# MCU.net
KiCad netlist of a schematic drawn in Altium Designer
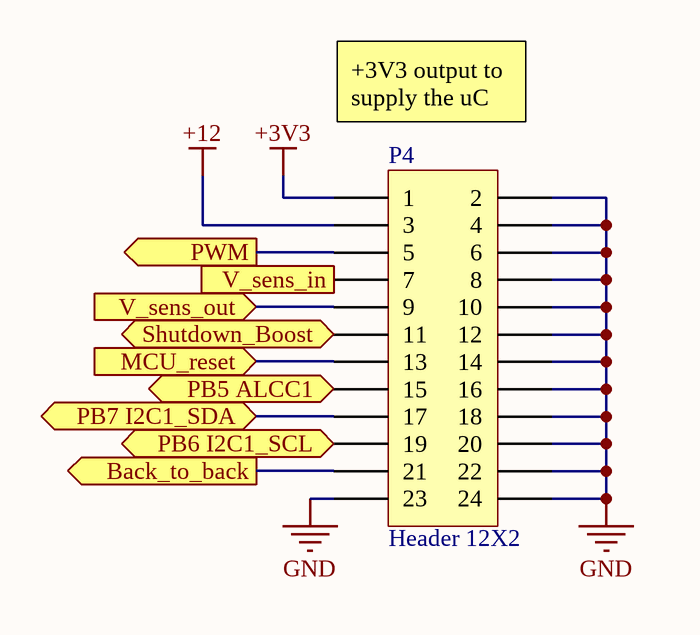
[diagram p0: MCU.SchDoc]

(export (version "E")
  (design (tool "Eeschema 10.0.6"))
  (components
    (comp (ref "P4")
      (value "Header 12X2")
      (footprint "HDR2X12")
      (description "Header, 12-Pin, Dual row")
      (fields (field (name "PUBLISHER") "Altium Limited"))
      (libsource (lib "Sch_Headers") (part "Header 12X2"))
    )
  )
  (nets
    (net (code "1") (name "+3V3") (class "Default")
      (node (ref "P4") (pin "1") (pinfunction "1_1") (pintype "passive"))
    )
    (net (code "2") (name "+12") (class "Default")
      (node (ref "P4") (pin "3") (pinfunction "3_3") (pintype "passive"))
    )
    (net (code "3") (name "/Back_to_back") (class "Default")
      (node (ref "P4") (pin "21") (pinfunction "21_21") (pintype "passive"))
    )
    (net (code "4") (name "/MCU_reset") (class "Default")
      (node (ref "P4") (pin "13") (pinfunction "13_13") (pintype "passive"))
    )
    (net (code "5") (name "/PB5 ALCC1") (class "Default")
      (node (ref "P4") (pin "15") (pinfunction "15_15") (pintype "passive"))
    )
    (net (code "6") (name "/PB6 I2C1_SCL") (class "Default")
      (node (ref "P4") (pin "19") (pinfunction "19_19") (pintype "passive"))
    )
    (net (code "7") (name "/PB7 I2C1_SDA") (class "Default")
      (node (ref "P4") (pin "17") (pinfunction "17_17") (pintype "passive"))
    )
    (net (code "8") (name "/PWM") (class "Default")
      (node (ref "P4") (pin "5") (pinfunction "5_5") (pintype "passive"))
    )
    (net (code "9") (name "/Shutdown_Boost") (class "Default")
      (node (ref "P4") (pin "11") (pinfunction "11_11") (pintype "passive"))
    )
    (net (code "10") (name "/V_sens_in") (class "Default")
      (node (ref "P4") (pin "7") (pinfunction "7_7") (pintype "passive"))
    )
    (net (code "11") (name "/V_sens_out") (class "Default")
      (node (ref "P4") (pin "9") (pinfunction "9_9") (pintype "passive"))
    )
    (net (code "12") (name "GND") (class "Default")
      (node (ref "P4") (pin "10") (pinfunction "10_10") (pintype "passive"))
      (node (ref "P4") (pin "12") (pinfunction "12_12") (pintype "passive"))
      (node (ref "P4") (pin "14") (pinfunction "14_14") (pintype "passive"))
      (node (ref "P4") (pin "16") (pinfunction "16_16") (pintype "passive"))
      (node (ref "P4") (pin "18") (pinfunction "18_18") (pintype "passive"))
      (node (ref "P4") (pin "2") (pinfunction "2_2") (pintype "passive"))
      (node (ref "P4") (pin "20") (pinfunction "20_20") (pintype "passive"))
      (node (ref "P4") (pin "22") (pinfunction "22_22") (pintype "passive"))
      (node (ref "P4") (pin "23") (pinfunction "23_23") (pintype "passive"))
      (node (ref "P4") (pin "24") (pinfunction "24_24") (pintype "passive"))
      (node (ref "P4") (pin "4") (pinfunction "4_4") (pintype "passive"))
      (node (ref "P4") (pin "6") (pinfunction "6_6") (pintype "passive"))
      (node (ref "P4") (pin "8") (pinfunction "8_8") (pintype "passive"))
    )
  )
)
